# SCH.net
KiCad netlist of a schematic drawn in Altium Designer
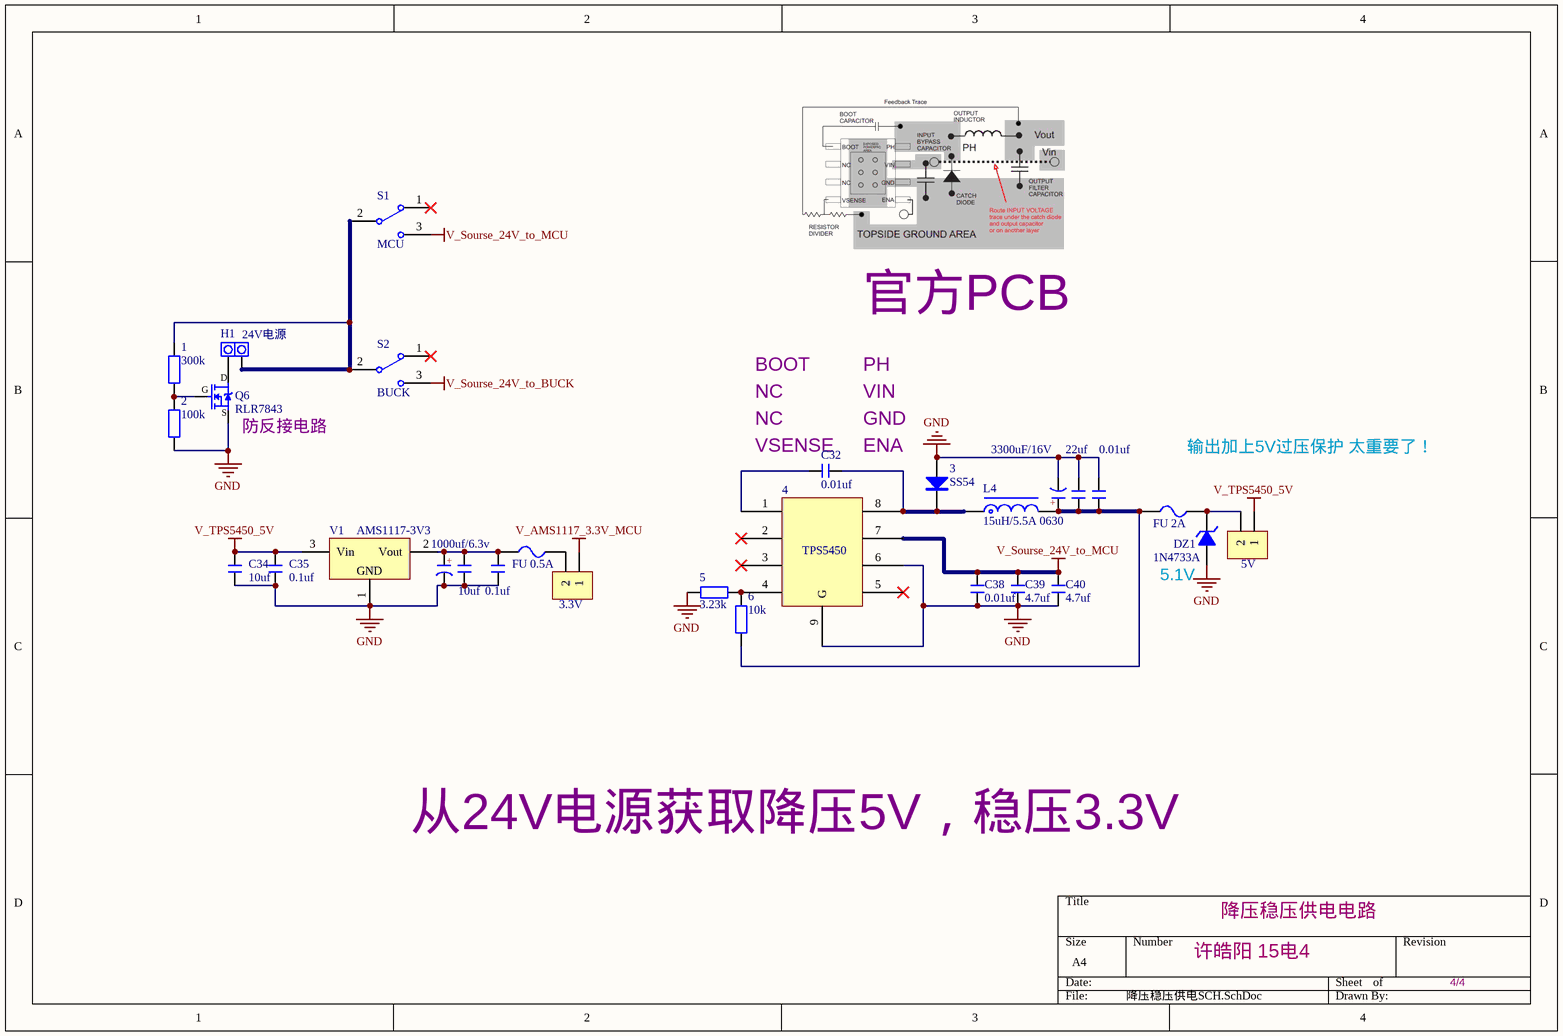
[diagram p0: 降压稳压供电SCH.SchDoc]

(export (version "E")
  (design (tool "Eeschema 10.0.6"))
  (components
    (comp (ref "1")
      (value "300k")
      (footprint "R 0805_M")
      (description "贴片电阻")
      (libsource (lib "3.1   - 电阻-电容-电感") (part "R"))
    )
    (comp (ref "2")
      (value "100k")
      (footprint "R 0805_M")
      (description "贴片电阻")
      (libsource (lib "3.1   - 电阻-电容-电感") (part "R"))
    )
    (comp (ref "3")
      (value "SS54")
      (footprint "SMA")
      (description "肖特基二极管")
      (libsource (lib "8.1   - 二极管-整流桥") (part "SS34"))
    )
    (comp (ref "4") (value "TPS5450") (footprint "ESOP8_M") (libsource (lib "IC_temp") (part "ESOP8")))
    (comp (ref "5")
      (value "3.23k")
      (footprint "R 0805_M")
      (description "贴片电阻")
      (libsource (lib "3.1   - 电阻-电容-电感") (part "R"))
    )
    (comp (ref "6")
      (value "10k")
      (footprint "R 0805_M")
      (description "贴片电阻")
      (libsource (lib "3.1   - 电阻-电容-电感") (part "R"))
    )
    (comp (ref "C32")
      (value "0.01uf")
      (footprint "C 0805_M")
      (description "无极性贴片电容")
      (libsource (lib "3.1   - 电阻-电容-电感") (part "C"))
    )
    (comp (ref "C33")
      (value "0.01uf")
      (footprint "C 0805_M")
      (description "无极性贴片电容")
      (libsource (lib "3.1   - 电阻-电容-电感") (part "C"))
    )
    (comp (ref "C34")
      (value "10uf")
      (footprint "C 0805_M")
      (description "无极性贴片电容")
      (libsource (lib "3.1   - 电阻-电容-电感") (part "C"))
    )
    (comp (ref "C35")
      (value "0.1uf")
      (footprint "C 0805_M")
      (description "无极性贴片电容")
      (libsource (lib "3.1   - 电阻-电容-电感") (part "C"))
    )
    (comp (ref "C36")
      (value "10uf")
      (footprint "C 0805_M")
      (description "无极性贴片电容")
      (libsource (lib "3.1   - 电阻-电容-电感") (part "C"))
    )
    (comp (ref "C36.")
      (value "22uf")
      (footprint "C 0805_M")
      (description "无极性贴片电容")
      (libsource (lib "3.1   - 电阻-电容-电感") (part "C"))
    )
    (comp (ref "C37")
      (value "0.1uf")
      (footprint "C 0805_M")
      (description "无极性贴片电容")
      (libsource (lib "3.1   - 电阻-电容-电感") (part "C"))
    )
    (comp (ref "C38")
      (value "0.01uf")
      (footprint "C 0805_M")
      (description "无极性贴片电容")
      (libsource (lib "3.1   - 电阻-电容-电感") (part "C"))
    )
    (comp (ref "C39")
      (value "4.7uf")
      (footprint "C 0805_M")
      (description "无极性贴片电容")
      (libsource (lib "3.1   - 电阻-电容-电感") (part "C"))
    )
    (comp (ref "C40")
      (value "4.7uf")
      (footprint "C 0805_M")
      (description "无极性贴片电容")
      (libsource (lib "3.1   - 电阻-电容-电感") (part "C"))
    )
    (comp (ref "DZ1")
      (value "1N4733A")
      (footprint "DO-35")
      (description "3.3V/0.5W稳压管")
      (libsource (lib "8.1   - 二极管-整流桥") (part "1N4620"))
    )
    (comp (ref "E1")
      (value "3300uF/16V")
      (footprint "DIP2")
      (description "直插电解电容")
      (libsource (lib "3.1   - 电阻-电容-电感") (part "C-CAP"))
    )
    (comp (ref "E2")
      (value "1000uf/6.3v")
      (footprint "DIP2-3.5mm")
      (description "直插电解电容")
      (libsource (lib "3.1   - 电阻-电容-电感") (part "C-CAP"))
    )
    (comp (ref "F2")
      (value "FU 2A")
      (footprint "FU 1812")
      (description "贴片保险丝")
      (libsource (lib "10.1 - 保险丝-晶振") (part "FU"))
    )
    (comp (ref "F3")
      (value "FU 0.5A")
      (footprint "FU 1206")
      (description "贴片保险丝")
      (libsource (lib "10.1 - 保险丝-晶振") (part "FU"))
    )
    (comp (ref "H1")
      (value "24V电源")
      (footprint "T_head")
      (description "引线焊盘")
      (libsource (lib "15.1 - 未分类器件") (part "PAD2"))
    )
    (comp (ref "JP10")
      (value "5V")
      (footprint "HDR2.54-LI-2P")
      (description "2P接插件")
      (libsource (lib "4.5   - 接插件-脚距2.54") (part "Header 2"))
    )
    (comp (ref "JP11")
      (value "3.3V")
      (footprint "HDR2.54-LI-2P")
      (description "2P接插件")
      (libsource (lib "4.5   - 接插件-脚距2.54") (part "Header 2"))
    )
    (comp (ref "L4")
      (value "15uH/5.5A 0630")
      (footprint "L-SMD-0630")
      (description "功率屏蔽电感")
      (libsource (lib "3.1   - 电阻-电容-电感") (part "L-CDRH"))
    )
    (comp (ref "Q6")
      (value "RLR7843")
      (footprint "TO252")
      (description "N沟道 60V/12A")
      (libsource (lib "6.1   - 场效应管-可控硅") (part "2SK3615"))
    )
    (comp (ref "S1")
      (value "MCU")
      (footprint "SK-12D07VG3")
      (description "1路波动开关")
      (libsource (lib "5.1   - 按键-开关") (part "SSW-1P"))
    )
    (comp (ref "S2")
      (value "BUCK")
      (footprint "MTS-10x")
      (description "MTS10x系列3脚扭子开关")
      (libsource (lib "5.1   - 按键-开关") (part "MTS-10x"))
    )
    (comp (ref "V1")
      (value "AMS1117-3V3")
      (footprint "SOT89_M")
      (description "三端稳压芯片")
      (libsource (lib "1.3   - 电源类芯片") (part "AMS1117"))
    )
  )
  (nets
    (net (code "1") (name "GND") (class "Default")
      (node (ref "2") (pin "1") (pinfunction "1_1") (pintype "passive"))
      (node (ref "3") (pin "1") (pinfunction "A_1") (pintype "passive"))
      (node (ref "4") (pin "6") (pinfunction "6_6") (pintype "power_in"))
      (node (ref "4") (pin "9") (pinfunction "G_9") (pintype "power_in"))
      (node (ref "5") (pin "1") (pinfunction "1_1") (pintype "passive"))
      (node (ref "C33") (pin "2") (pinfunction "2_2") (pintype "passive"))
      (node (ref "C34") (pin "2") (pinfunction "2_2") (pintype "passive"))
      (node (ref "C35") (pin "2") (pinfunction "2_2") (pintype "passive"))
      (node (ref "C36") (pin "2") (pinfunction "2_2") (pintype "passive"))
      (node (ref "C36.") (pin "1") (pinfunction "1_1") (pintype "passive"))
      (node (ref "C37") (pin "2") (pinfunction "2_2") (pintype "passive"))
      (node (ref "C38") (pin "1") (pinfunction "1_1") (pintype "passive"))
      (node (ref "C39") (pin "1") (pinfunction "1_1") (pintype "passive"))
      (node (ref "C40") (pin "1") (pinfunction "1_1") (pintype "passive"))
      (node (ref "DZ1") (pin "1") (pinfunction "A_1") (pintype "passive"))
      (node (ref "E1") (pin "2") (pinfunction "K_2") (pintype "passive"))
      (node (ref "E2") (pin "2") (pinfunction "K_2") (pintype "passive"))
      (node (ref "Q6") (pin "3") (pinfunction "S_3") (pintype "passive"))
      (node (ref "V1") (pin "1") (pinfunction "GND_1") (pintype "passive"))
    )
    (net (code "2") (name "Net-(1-Pad2)") (class "Default")
      (node (ref "1") (pin "2") (pinfunction "2_2") (pintype "passive"))
      (node (ref "H1") (pin "2") (pinfunction "2_2") (pintype "passive"))
      (node (ref "S1") (pin "2") (pinfunction "2_2") (pintype "passive"))
      (node (ref "S2") (pin "2") (pinfunction "2_2") (pintype "passive"))
    )
    (net (code "3") (name "Net-(3-K)") (class "Default")
      (node (ref "3") (pin "2") (pinfunction "K_2") (pintype "passive"))
      (node (ref "4") (pin "8") (pinfunction "8_8") (pintype "power_in"))
      (node (ref "C32") (pin "2") (pinfunction "2_2") (pintype "passive"))
      (node (ref "L4") (pin "1") (pinfunction "1_1") (pintype "passive"))
    )
    (net (code "4") (name "Net-(4-Pad1)") (class "Default")
      (node (ref "4") (pin "1") (pinfunction "1_1") (pintype "power_in"))
      (node (ref "C32") (pin "1") (pinfunction "1_1") (pintype "passive"))
    )
    (net (code "5") (name "Net-(4-Pad4)") (class "Default")
      (node (ref "4") (pin "4") (pinfunction "4_4") (pintype "power_in"))
      (node (ref "5") (pin "2") (pinfunction "2_2") (pintype "passive"))
      (node (ref "6") (pin "1") (pinfunction "1_1") (pintype "passive"))
    )
    (net (code "6") (name "Net-(DZ1-K)") (class "Default")
      (node (ref "DZ1") (pin "2") (pinfunction "K_2") (pintype "passive"))
      (node (ref "F2") (pin "2") (pinfunction "2_2") (pintype "passive"))
      (node (ref "JP10") (pin "2") (pinfunction "2_2") (pintype "passive"))
    )
    (net (code "7") (name "Net-(E1-A)") (class "Default")
      (node (ref "6") (pin "2") (pinfunction "2_2") (pintype "passive"))
      (node (ref "C33") (pin "1") (pinfunction "1_1") (pintype "passive"))
      (node (ref "C36.") (pin "2") (pinfunction "2_2") (pintype "passive"))
      (node (ref "E1") (pin "1") (pinfunction "A_1") (pintype "passive"))
      (node (ref "F2") (pin "1") (pinfunction "1_1") (pintype "passive"))
      (node (ref "L4") (pin "2") (pinfunction "2_2") (pintype "passive"))
    )
    (net (code "8") (name "Net-(E2-A)") (class "Default")
      (node (ref "C36") (pin "1") (pinfunction "1_1") (pintype "passive"))
      (node (ref "C37") (pin "1") (pinfunction "1_1") (pintype "passive"))
      (node (ref "E2") (pin "1") (pinfunction "A_1") (pintype "passive"))
      (node (ref "F3") (pin "1") (pinfunction "1_1") (pintype "passive"))
      (node (ref "V1") (pin "2") (pinfunction "Vout_2") (pintype "passive"))
    )
    (net (code "9") (name "Net-(F3-Pad2)") (class "Default")
      (node (ref "F3") (pin "2") (pinfunction "2_2") (pintype "passive"))
      (node (ref "JP11") (pin "2") (pinfunction "2_2") (pintype "passive"))
    )
    (net (code "10") (name "Net-(Q6-D)") (class "Default")
      (node (ref "H1") (pin "1") (pinfunction "1_1") (pintype "passive"))
      (node (ref "Q6") (pin "2") (pinfunction "D_2") (pintype "passive"))
    )
    (net (code "11") (name "Net-(Q6-G)") (class "Default")
      (node (ref "1") (pin "1") (pinfunction "1_1") (pintype "passive"))
      (node (ref "2") (pin "2") (pinfunction "2_2") (pintype "passive"))
      (node (ref "Q6") (pin "1") (pinfunction "G_1") (pintype "passive"))
    )
    (net (code "12") (name "V_AMS1117_3.3V_MCU") (class "Default")
      (node (ref "JP11") (pin "1") (pinfunction "1_1") (pintype "passive"))
    )
    (net (code "13") (name "V_Sourse_24V_to_BUCK") (class "Default")
      (node (ref "S2") (pin "3") (pinfunction "3_3") (pintype "passive"))
    )
    (net (code "14") (name "V_Sourse_24V_to_MCU") (class "Default")
      (node (ref "4") (pin "7") (pinfunction "7_7") (pintype "power_in"))
      (node (ref "C38") (pin "2") (pinfunction "2_2") (pintype "passive"))
      (node (ref "C39") (pin "2") (pinfunction "2_2") (pintype "passive"))
      (node (ref "C40") (pin "2") (pinfunction "2_2") (pintype "passive"))
      (node (ref "S1") (pin "3") (pinfunction "3_3") (pintype "passive"))
    )
    (net (code "15") (name "V_TPS5450_5V") (class "Default")
      (node (ref "C34") (pin "1") (pinfunction "1_1") (pintype "passive"))
      (node (ref "C35") (pin "1") (pinfunction "1_1") (pintype "passive"))
      (node (ref "JP10") (pin "1") (pinfunction "1_1") (pintype "passive"))
      (node (ref "V1") (pin "3") (pinfunction "Vin_3") (pintype "passive"))
    )
    (net (code "16") (name "unconnected-(4-Pad2)") (class "Default")
      (node (ref "4") (pin "2") (pinfunction "2_2") (pintype "power_in+no_connect"))
    )
    (net (code "17") (name "unconnected-(4-Pad3)") (class "Default")
      (node (ref "4") (pin "3") (pinfunction "3_3") (pintype "power_in+no_connect"))
    )
    (net (code "18") (name "unconnected-(4-Pad5)") (class "Default")
      (node (ref "4") (pin "5") (pinfunction "5_5") (pintype "power_in+no_connect"))
    )
    (net (code "19") (name "unconnected-(S1-Pad1)") (class "Default")
      (node (ref "S1") (pin "1") (pinfunction "1_1") (pintype "passive+no_connect"))
    )
    (net (code "20") (name "unconnected-(S2-Pad1)") (class "Default")
      (node (ref "S2") (pin "1") (pinfunction "1_1") (pintype "passive+no_connect"))
    )
  )
)
